# Individual_Band.net
KiCad netlist of a schematic drawn in Altium Designer
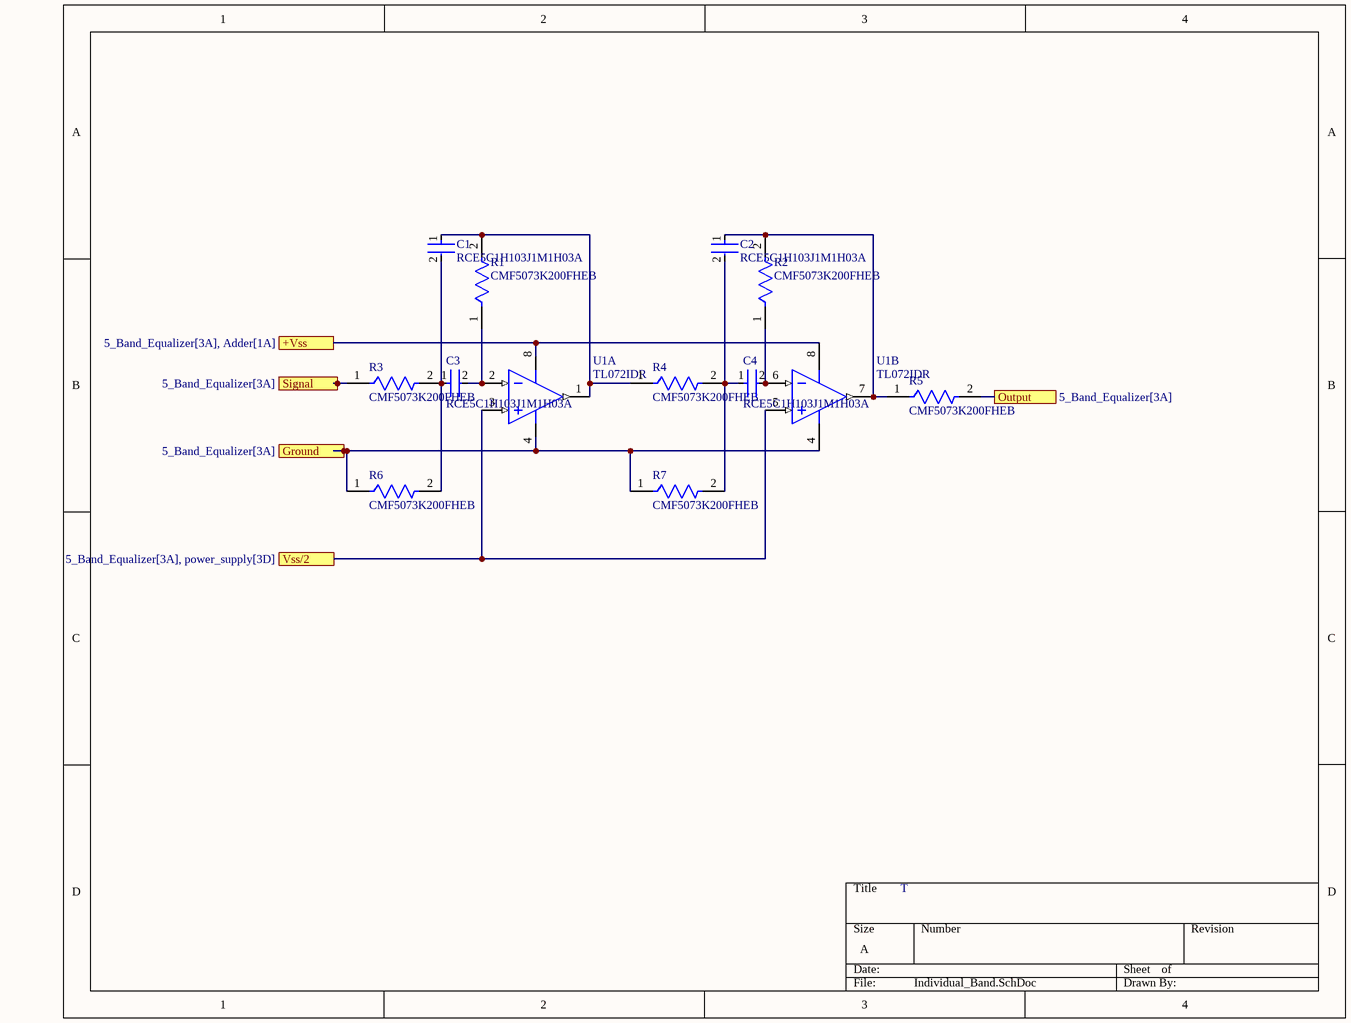
[diagram p0: Individual_Band.SchDoc]

(export (version "E")
  (design (tool "Eeschema 10.0.6"))
  (components
    (comp (ref "C1")
      (value "RCE5C1H103J1M1H03A")
      (footprint "FP-RCE1K1-2_5-MFG")
      (description "Cap Ceramic Monolithic 10nF 50V 5% Thru-Hole Bulk")
      (fields (field (name "VOLTAGE") "50V") (field (name "TOLERANCE") "5%"))
      (libsource (lib "Altium Content Vault") (part "02cd4be3c70576c341d710602a673aa"))
    )
    (comp (ref "C2")
      (value "RCE5C1H103J1M1H03A")
      (footprint "FP-RCE1K1-2_5-MFG")
      (description "Cap Ceramic Monolithic 10nF 50V 5% Thru-Hole Bulk")
      (fields (field (name "VOLTAGE") "50V") (field (name "TOLERANCE") "5%"))
      (libsource (lib "Altium Content Vault") (part "02cd4be3c70576c341d710602a673aa"))
    )
    (comp (ref "C3")
      (value "RCE5C1H103J1M1H03A")
      (footprint "FP-RCE1K1-2_5-MFG")
      (description "Cap Ceramic Monolithic 10nF 50V 5% Thru-Hole Bulk")
      (fields (field (name "VOLTAGE") "50V") (field (name "TOLERANCE") "5%"))
      (libsource (lib "Altium Content Vault") (part "02cd4be3c70576c341d710602a673aa"))
    )
    (comp (ref "C4")
      (value "RCE5C1H103J1M1H03A")
      (footprint "FP-RCE1K1-2_5-MFG")
      (description "Cap Ceramic Monolithic 10nF 50V 5% Thru-Hole Bulk")
      (fields (field (name "VOLTAGE") "50V") (field (name "TOLERANCE") "5%"))
      (libsource (lib "Altium Content Vault") (part "02cd4be3c70576c341d710602a673aa"))
    )
    (comp (ref "R1")
      (value "CMF5073K200FHEB")
      (footprint "FP-CMF50-0")
      (description "CMF5073K200FHEB Res Metal Film 73.2K Ohm 1% 0.125W(1/8W) ±50ppm/°C Epoxy AXL T/R")
      (fields (field (name "TOLERANCE") "1%"))
      (libsource (lib "Altium Content Vault") (part "1029c3af85768c4190bb7ad29bc67b5"))
    )
    (comp (ref "R2")
      (value "CMF5073K200FHEB")
      (footprint "FP-CMF50-0")
      (description "CMF5073K200FHEB Res Metal Film 73.2K Ohm 1% 0.125W(1/8W) ±50ppm/°C Epoxy AXL T/R")
      (fields (field (name "TOLERANCE") "1%"))
      (libsource (lib "Altium Content Vault") (part "1029c3af85768c4190bb7ad29bc67b5"))
    )
    (comp (ref "R3")
      (value "CMF5073K200FHEB")
      (footprint "FP-CMF50-0")
      (description "CMF5073K200FHEB Res Metal Film 73.2K Ohm 1% 0.125W(1/8W) ±50ppm/°C Epoxy AXL T/R")
      (fields (field (name "TOLERANCE") "1%"))
      (libsource (lib "Altium Content Vault") (part "1029c3af85768c4190bb7ad29bc67b5"))
    )
    (comp (ref "R4")
      (value "CMF5073K200FHEB")
      (footprint "FP-CMF50-0")
      (description "CMF5073K200FHEB Res Metal Film 73.2K Ohm 1% 0.125W(1/8W) ±50ppm/°C Epoxy AXL T/R")
      (fields (field (name "TOLERANCE") "1%"))
      (libsource (lib "Altium Content Vault") (part "1029c3af85768c4190bb7ad29bc67b5"))
    )
    (comp (ref "R5")
      (value "CMF5073K200FHEB")
      (footprint "FP-CMF50-0")
      (description "CMF5073K200FHEB Res Metal Film 73.2K Ohm 1% 0.125W(1/8W) ±50ppm/°C Epoxy AXL T/R")
      (fields (field (name "TOLERANCE") "1%"))
      (libsource (lib "Altium Content Vault") (part "1029c3af85768c4190bb7ad29bc67b5"))
    )
    (comp (ref "R6")
      (value "CMF5073K200FHEB")
      (footprint "FP-CMF50-0")
      (description "CMF5073K200FHEB Res Metal Film 73.2K Ohm 1% 0.125W(1/8W) ±50ppm/°C Epoxy AXL T/R")
      (fields (field (name "TOLERANCE") "1%"))
      (libsource (lib "Altium Content Vault") (part "1029c3af85768c4190bb7ad29bc67b5"))
    )
    (comp (ref "R7")
      (value "CMF5073K200FHEB")
      (footprint "FP-CMF50-0")
      (description "CMF5073K200FHEB Res Metal Film 73.2K Ohm 1% 0.125W(1/8W) ±50ppm/°C Epoxy AXL T/R")
      (fields (field (name "TOLERANCE") "1%"))
      (libsource (lib "Altium Content Vault") (part "1029c3af85768c4190bb7ad29bc67b5"))
    )
    (comp (ref "U1")
      (value "TL072IDR")
      (footprint "D0008A_L")
      (fields (field (name "MANUFACTURER") "Texas Instruments"))
      (libsource (lib "Altium Content Vault") (part "TI-AMP-D6-2-8_D"))
    )
  )
  (nets
    (net (code "1") (name "/+Vss") (class "Default")
      (node (ref "U1") (pin "8") (pinfunction "VCC+_8") (pintype "power_in"))
    )
    (net (code "2") (name "/Ground") (class "Default")
      (node (ref "R6") (pin "1") (pinfunction "1_1") (pintype "passive"))
      (node (ref "R7") (pin "1") (pinfunction "1_1") (pintype "passive"))
      (node (ref "U1") (pin "4") (pinfunction "VCC-_4") (pintype "power_in"))
    )
    (net (code "3") (name "/Output") (class "Default")
      (node (ref "R5") (pin "2") (pinfunction "2_2") (pintype "passive"))
    )
    (net (code "4") (name "/Signal") (class "Default")
      (node (ref "R3") (pin "1") (pinfunction "1_1") (pintype "passive"))
    )
    (net (code "5") (name "/Vss{slash}2") (class "Default")
      (node (ref "U1") (pin "3") (pinfunction "IN1+_3") (pintype "input"))
      (node (ref "U1") (pin "5") (pinfunction "IN2+_5") (pintype "input"))
    )
    (net (code "6") (name "Net-(C1-Pad2)") (class "Default")
      (node (ref "C1") (pin "2") (pinfunction "2_2") (pintype "passive"))
      (node (ref "C3") (pin "1") (pinfunction "1_1") (pintype "passive"))
      (node (ref "R3") (pin "2") (pinfunction "2_2") (pintype "passive"))
      (node (ref "R6") (pin "2") (pinfunction "2_2") (pintype "passive"))
    )
    (net (code "7") (name "Net-(C2-Pad2)") (class "Default")
      (node (ref "C2") (pin "2") (pinfunction "2_2") (pintype "passive"))
      (node (ref "C4") (pin "1") (pinfunction "1_1") (pintype "passive"))
      (node (ref "R4") (pin "2") (pinfunction "2_2") (pintype "passive"))
      (node (ref "R7") (pin "2") (pinfunction "2_2") (pintype "passive"))
    )
    (net (code "8") (name "Net-(U1A-IN1-)") (class "Default")
      (node (ref "C3") (pin "2") (pinfunction "2_2") (pintype "passive"))
      (node (ref "R1") (pin "1") (pinfunction "1_1") (pintype "passive"))
      (node (ref "U1") (pin "2") (pinfunction "IN1-_2") (pintype "input"))
    )
    (net (code "9") (name "Net-(U1A-OUT1)") (class "Default")
      (node (ref "C1") (pin "1") (pinfunction "1_1") (pintype "passive"))
      (node (ref "R1") (pin "2") (pinfunction "2_2") (pintype "passive"))
      (node (ref "R4") (pin "1") (pinfunction "1_1") (pintype "passive"))
      (node (ref "U1") (pin "1") (pinfunction "OUT1_1") (pintype "output"))
    )
    (net (code "10") (name "Net-(U1B-IN2-)") (class "Default")
      (node (ref "C4") (pin "2") (pinfunction "2_2") (pintype "passive"))
      (node (ref "R2") (pin "1") (pinfunction "1_1") (pintype "passive"))
      (node (ref "U1") (pin "6") (pinfunction "IN2-_6") (pintype "input"))
    )
    (net (code "11") (name "Net-(U1B-OUT2)") (class "Default")
      (node (ref "C2") (pin "1") (pinfunction "1_1") (pintype "passive"))
      (node (ref "R2") (pin "2") (pinfunction "2_2") (pintype "passive"))
      (node (ref "R5") (pin "1") (pinfunction "1_1") (pintype "passive"))
      (node (ref "U1") (pin "7") (pinfunction "OUT2_7") (pintype "output"))
    )
  )
)
